# 2022.net
KiCad netlist of a schematic drawn in EAGLE
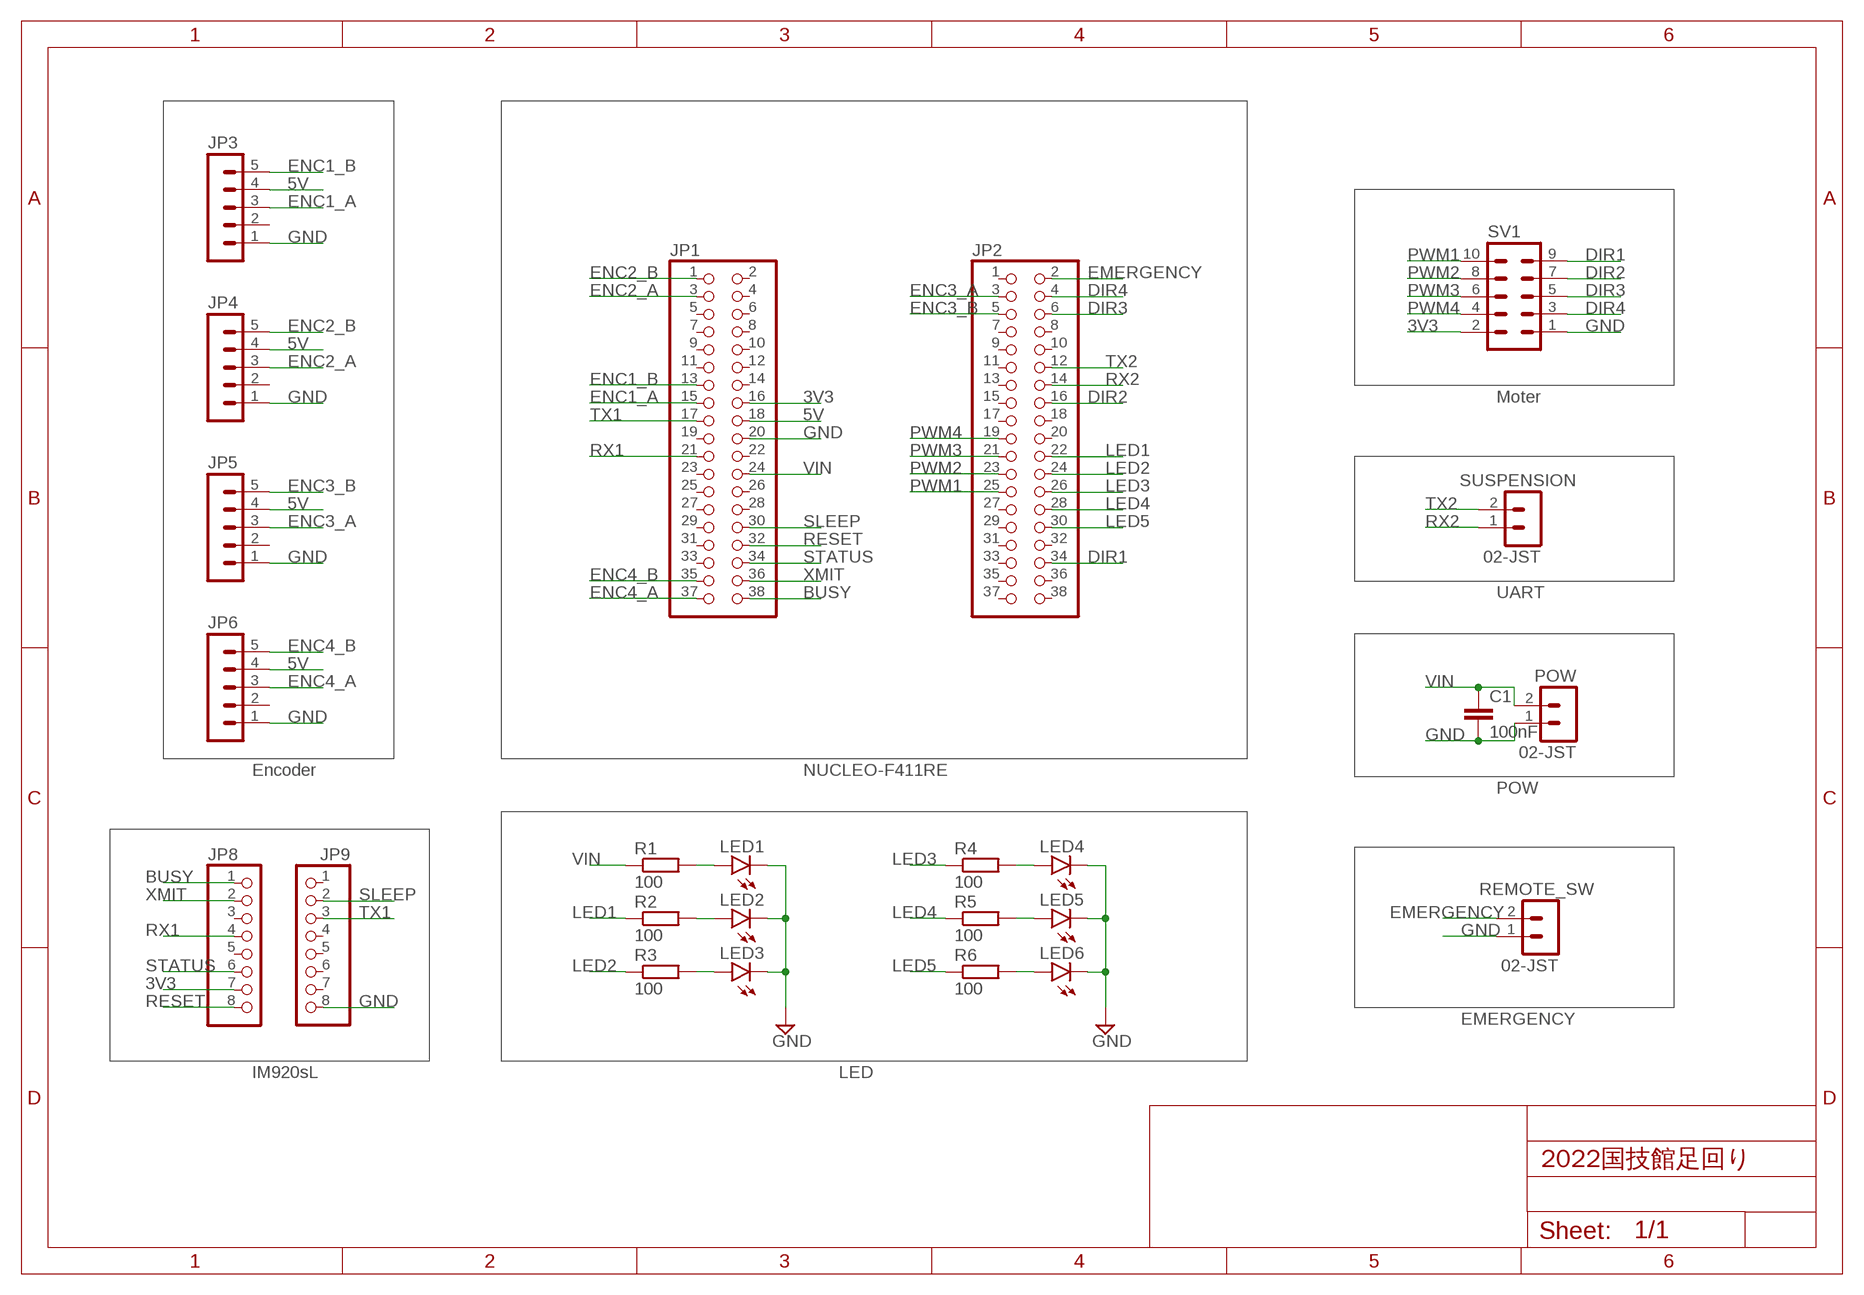
[diagram p0: schematic, sheet 1]

(export (version "E")
  (design (tool "Eeschema 10.0.6"))
  (components
    (comp (ref "C1")
      (value "100nF")
      (footprint "eagle-import:C025-024X044")
      (libsource (lib "eagle-import") (part "C-EU025-024X044"))
    )
    (comp (ref "JP1")
      (value "PINHD-2X19")
      (footprint "eagle-import:2X19")
      (libsource (lib "eagle-import") (part "PINHD-2X19"))
    )
    (comp (ref "JP2")
      (value "PINHD-2X19")
      (footprint "eagle-import:2X19")
      (libsource (lib "eagle-import") (part "PINHD-2X19"))
    )
    (comp (ref "JP3")
      (value "05-JST")
      (footprint "eagle-import:B5B-XH")
      (libsource (lib "eagle-import") (part "05-JST"))
    )
    (comp (ref "JP4")
      (value "05-JST")
      (footprint "eagle-import:B5B-XH")
      (libsource (lib "eagle-import") (part "05-JST"))
    )
    (comp (ref "JP5")
      (value "05-JST")
      (footprint "eagle-import:B5B-XH")
      (libsource (lib "eagle-import") (part "05-JST"))
    )
    (comp (ref "JP6")
      (value "05-JST")
      (footprint "eagle-import:B5B-XH")
      (libsource (lib "eagle-import") (part "05-JST"))
    )
    (comp (ref "JP8")
      (value "PINHD-1X8")
      (footprint "eagle-import:1X08")
      (libsource (lib "eagle-import") (part "PINHD-1X8"))
    )
    (comp (ref "JP9")
      (value "PINHD-1X8")
      (footprint "eagle-import:1X08")
      (libsource (lib "eagle-import") (part "PINHD-1X8"))
    )
    (comp (ref "LED1")
      (value "LED5MM")
      (footprint "eagle-import:LED5MM")
      (libsource (lib "eagle-import") (part "LED5MM"))
    )
    (comp (ref "LED2")
      (value "LED5MM")
      (footprint "eagle-import:LED5MM")
      (libsource (lib "eagle-import") (part "LED5MM"))
    )
    (comp (ref "LED3")
      (value "LED5MM")
      (footprint "eagle-import:LED5MM")
      (libsource (lib "eagle-import") (part "LED5MM"))
    )
    (comp (ref "LED4")
      (value "LED5MM")
      (footprint "eagle-import:LED5MM")
      (libsource (lib "eagle-import") (part "LED5MM"))
    )
    (comp (ref "LED5")
      (value "LED5MM")
      (footprint "eagle-import:LED5MM")
      (libsource (lib "eagle-import") (part "LED5MM"))
    )
    (comp (ref "LED6")
      (value "LED5MM")
      (footprint "eagle-import:LED5MM")
      (libsource (lib "eagle-import") (part "LED5MM"))
    )
    (comp (ref "POW")
      (value "02-JST")
      (footprint "eagle-import:B2B-XH")
      (libsource (lib "eagle-import") (part "02-JST"))
    )
    (comp (ref "R1")
      (value "100")
      (footprint "eagle-import:0204_7")
      (libsource (lib "eagle-import") (part "R-EU_0204/7"))
    )
    (comp (ref "R2")
      (value "100")
      (footprint "eagle-import:0207_2V")
      (libsource (lib "eagle-import") (part "R-EU_0207/2V"))
    )
    (comp (ref "R3")
      (value "100")
      (footprint "eagle-import:0207_2V")
      (libsource (lib "eagle-import") (part "R-EU_0207/2V"))
    )
    (comp (ref "R4")
      (value "100")
      (footprint "eagle-import:0207_2V")
      (libsource (lib "eagle-import") (part "R-EU_0207/2V"))
    )
    (comp (ref "R5")
      (value "100")
      (footprint "eagle-import:0207_2V")
      (libsource (lib "eagle-import") (part "R-EU_0207/2V"))
    )
    (comp (ref "R6")
      (value "100")
      (footprint "eagle-import:0207_2V")
      (libsource (lib "eagle-import") (part "R-EU_0207/2V"))
    )
    (comp (ref "REMOTE_SW")
      (value "02-JST")
      (footprint "eagle-import:B2B-XH")
      (libsource (lib "eagle-import") (part "02-JST"))
    )
    (comp (ref "SUSPENSION")
      (value "02-JST")
      (footprint "eagle-import:B2B-XH")
      (libsource (lib "eagle-import") (part "02-JST"))
    )
    (comp (ref "SV1")
      (value "ML10")
      (footprint "eagle-import:ML10")
      (libsource (lib "eagle-import") (part "ML10"))
    )
  )
  (nets
    (net (code "1") (name "/3V3") (class "Default")
      (node (ref "JP1") (pin "16") (pinfunction "16_16") (pintype "passive"))
      (node (ref "JP8") (pin "7") (pinfunction "7_7") (pintype "passive"))
      (node (ref "SV1") (pin "2") (pinfunction "2_2") (pintype "passive"))
    )
    (net (code "2") (name "/5V") (class "Default")
      (node (ref "JP1") (pin "18") (pinfunction "18_18") (pintype "passive"))
      (node (ref "JP3") (pin "4") (pinfunction "4_4") (pintype "passive"))
      (node (ref "JP4") (pin "4") (pinfunction "4_4") (pintype "passive"))
      (node (ref "JP5") (pin "4") (pinfunction "4_4") (pintype "passive"))
      (node (ref "JP6") (pin "4") (pinfunction "4_4") (pintype "passive"))
    )
    (net (code "3") (name "/BUSY") (class "Default")
      (node (ref "JP1") (pin "38") (pinfunction "38_38") (pintype "passive"))
      (node (ref "JP8") (pin "1") (pinfunction "1_1") (pintype "passive"))
    )
    (net (code "4") (name "/DIR1") (class "Default")
      (node (ref "JP2") (pin "34") (pinfunction "34_34") (pintype "passive"))
      (node (ref "SV1") (pin "9") (pinfunction "9_9") (pintype "passive"))
    )
    (net (code "5") (name "/DIR2") (class "Default")
      (node (ref "JP2") (pin "16") (pinfunction "16_16") (pintype "passive"))
      (node (ref "SV1") (pin "7") (pinfunction "7_7") (pintype "passive"))
    )
    (net (code "6") (name "/DIR3") (class "Default")
      (node (ref "JP2") (pin "6") (pinfunction "6_6") (pintype "passive"))
      (node (ref "SV1") (pin "5") (pinfunction "5_5") (pintype "passive"))
    )
    (net (code "7") (name "/DIR4") (class "Default")
      (node (ref "JP2") (pin "4") (pinfunction "4_4") (pintype "passive"))
      (node (ref "SV1") (pin "3") (pinfunction "3_3") (pintype "passive"))
    )
    (net (code "8") (name "/EMERGENCY") (class "Default")
      (node (ref "JP2") (pin "2") (pinfunction "2_2") (pintype "passive"))
      (node (ref "REMOTE_SW") (pin "2") (pinfunction "2_2") (pintype "passive"))
    )
    (net (code "9") (name "/ENC1_A") (class "Default")
      (node (ref "JP1") (pin "15") (pinfunction "15_15") (pintype "passive"))
      (node (ref "JP3") (pin "3") (pinfunction "3_3") (pintype "passive"))
    )
    (net (code "10") (name "/ENC1_B") (class "Default")
      (node (ref "JP1") (pin "13") (pinfunction "13_13") (pintype "passive"))
      (node (ref "JP3") (pin "5") (pinfunction "5_5") (pintype "passive"))
    )
    (net (code "11") (name "/ENC2_A") (class "Default")
      (node (ref "JP1") (pin "3") (pinfunction "3_3") (pintype "passive"))
      (node (ref "JP4") (pin "3") (pinfunction "3_3") (pintype "passive"))
    )
    (net (code "12") (name "/ENC2_B") (class "Default")
      (node (ref "JP1") (pin "1") (pinfunction "1_1") (pintype "passive"))
      (node (ref "JP4") (pin "5") (pinfunction "5_5") (pintype "passive"))
    )
    (net (code "13") (name "/ENC3_A") (class "Default")
      (node (ref "JP2") (pin "3") (pinfunction "3_3") (pintype "passive"))
      (node (ref "JP5") (pin "3") (pinfunction "3_3") (pintype "passive"))
    )
    (net (code "14") (name "/ENC3_B") (class "Default")
      (node (ref "JP2") (pin "5") (pinfunction "5_5") (pintype "passive"))
      (node (ref "JP5") (pin "5") (pinfunction "5_5") (pintype "passive"))
    )
    (net (code "15") (name "/ENC4_A") (class "Default")
      (node (ref "JP1") (pin "37") (pinfunction "37_37") (pintype "passive"))
      (node (ref "JP6") (pin "3") (pinfunction "3_3") (pintype "passive"))
    )
    (net (code "16") (name "/ENC4_B") (class "Default")
      (node (ref "JP1") (pin "35") (pinfunction "35_35") (pintype "passive"))
      (node (ref "JP6") (pin "5") (pinfunction "5_5") (pintype "passive"))
    )
    (net (code "17") (name "/LED1") (class "Default")
      (node (ref "JP2") (pin "22") (pinfunction "22_22") (pintype "passive"))
      (node (ref "R2") (pin "1") (pinfunction "1_1") (pintype "passive"))
    )
    (net (code "18") (name "/LED2") (class "Default")
      (node (ref "JP2") (pin "24") (pinfunction "24_24") (pintype "passive"))
      (node (ref "R3") (pin "1") (pinfunction "1_1") (pintype "passive"))
    )
    (net (code "19") (name "/LED3") (class "Default")
      (node (ref "JP2") (pin "26") (pinfunction "26_26") (pintype "passive"))
      (node (ref "R4") (pin "1") (pinfunction "1_1") (pintype "passive"))
    )
    (net (code "20") (name "/LED4") (class "Default")
      (node (ref "JP2") (pin "28") (pinfunction "28_28") (pintype "passive"))
      (node (ref "R5") (pin "1") (pinfunction "1_1") (pintype "passive"))
    )
    (net (code "21") (name "/LED5") (class "Default")
      (node (ref "JP2") (pin "30") (pinfunction "30_30") (pintype "passive"))
      (node (ref "R6") (pin "1") (pinfunction "1_1") (pintype "passive"))
    )
    (net (code "22") (name "/PWM1") (class "Default")
      (node (ref "JP2") (pin "25") (pinfunction "25_25") (pintype "passive"))
      (node (ref "SV1") (pin "10") (pinfunction "10_10") (pintype "passive"))
    )
    (net (code "23") (name "/PWM2") (class "Default")
      (node (ref "JP2") (pin "23") (pinfunction "23_23") (pintype "passive"))
      (node (ref "SV1") (pin "8") (pinfunction "8_8") (pintype "passive"))
    )
    (net (code "24") (name "/PWM3") (class "Default")
      (node (ref "JP2") (pin "21") (pinfunction "21_21") (pintype "passive"))
      (node (ref "SV1") (pin "6") (pinfunction "6_6") (pintype "passive"))
    )
    (net (code "25") (name "/PWM4") (class "Default")
      (node (ref "JP2") (pin "19") (pinfunction "19_19") (pintype "passive"))
      (node (ref "SV1") (pin "4") (pinfunction "4_4") (pintype "passive"))
    )
    (net (code "26") (name "/RESET") (class "Default")
      (node (ref "JP1") (pin "32") (pinfunction "32_32") (pintype "passive"))
      (node (ref "JP8") (pin "8") (pinfunction "8_8") (pintype "passive"))
    )
    (net (code "27") (name "/RX1") (class "Default")
      (node (ref "JP1") (pin "21") (pinfunction "21_21") (pintype "passive"))
      (node (ref "JP8") (pin "4") (pinfunction "4_4") (pintype "passive"))
    )
    (net (code "28") (name "/RX2") (class "Default")
      (node (ref "JP2") (pin "14") (pinfunction "14_14") (pintype "passive"))
      (node (ref "SUSPENSION") (pin "1") (pinfunction "1_1") (pintype "passive"))
    )
    (net (code "29") (name "/SLEEP") (class "Default")
      (node (ref "JP1") (pin "30") (pinfunction "30_30") (pintype "passive"))
      (node (ref "JP9") (pin "2") (pinfunction "2_2") (pintype "passive"))
    )
    (net (code "30") (name "/STATUS") (class "Default")
      (node (ref "JP1") (pin "34") (pinfunction "34_34") (pintype "passive"))
      (node (ref "JP8") (pin "6") (pinfunction "6_6") (pintype "passive"))
    )
    (net (code "31") (name "/TX1") (class "Default")
      (node (ref "JP1") (pin "17") (pinfunction "17_17") (pintype "passive"))
      (node (ref "JP9") (pin "3") (pinfunction "3_3") (pintype "passive"))
    )
    (net (code "32") (name "/TX2") (class "Default")
      (node (ref "JP2") (pin "12") (pinfunction "12_12") (pintype "passive"))
      (node (ref "SUSPENSION") (pin "2") (pinfunction "2_2") (pintype "passive"))
    )
    (net (code "33") (name "/VIN") (class "Default")
      (node (ref "C1") (pin "1") (pinfunction "1_1") (pintype "passive"))
      (node (ref "JP1") (pin "24") (pinfunction "24_24") (pintype "passive"))
      (node (ref "POW") (pin "2") (pinfunction "2_2") (pintype "passive"))
      (node (ref "R1") (pin "1") (pinfunction "1_1") (pintype "passive"))
    )
    (net (code "34") (name "/XMIT") (class "Default")
      (node (ref "JP1") (pin "36") (pinfunction "36_36") (pintype "passive"))
      (node (ref "JP8") (pin "2") (pinfunction "2_2") (pintype "passive"))
    )
    (net (code "35") (name "GND") (class "Default")
      (node (ref "C1") (pin "2") (pinfunction "2_2") (pintype "passive"))
      (node (ref "JP1") (pin "20") (pinfunction "20_20") (pintype "passive"))
      (node (ref "JP3") (pin "1") (pinfunction "1_1") (pintype "passive"))
      (node (ref "JP4") (pin "1") (pinfunction "1_1") (pintype "passive"))
      (node (ref "JP5") (pin "1") (pinfunction "1_1") (pintype "passive"))
      (node (ref "JP6") (pin "1") (pinfunction "1_1") (pintype "passive"))
      (node (ref "JP9") (pin "8") (pinfunction "8_8") (pintype "passive"))
      (node (ref "LED1") (pin "K") (pinfunction "C_K") (pintype "passive"))
      (node (ref "LED2") (pin "K") (pinfunction "C_K") (pintype "passive"))
      (node (ref "LED3") (pin "K") (pinfunction "C_K") (pintype "passive"))
      (node (ref "LED4") (pin "K") (pinfunction "C_K") (pintype "passive"))
      (node (ref "LED5") (pin "K") (pinfunction "C_K") (pintype "passive"))
      (node (ref "LED6") (pin "K") (pinfunction "C_K") (pintype "passive"))
      (node (ref "POW") (pin "1") (pinfunction "1_1") (pintype "passive"))
      (node (ref "REMOTE_SW") (pin "1") (pinfunction "1_1") (pintype "passive"))
      (node (ref "SV1") (pin "1") (pinfunction "1_1") (pintype "passive"))
    )
    (net (code "36") (name "Net-(LED1-PadA)") (class "Default")
      (node (ref "LED1") (pin "A") (pinfunction "A_A") (pintype "passive"))
      (node (ref "R1") (pin "2") (pinfunction "2_2") (pintype "passive"))
    )
    (net (code "37") (name "Net-(LED2-PadA)") (class "Default")
      (node (ref "LED2") (pin "A") (pinfunction "A_A") (pintype "passive"))
      (node (ref "R2") (pin "2") (pinfunction "2_2") (pintype "passive"))
    )
    (net (code "38") (name "Net-(LED3-PadA)") (class "Default")
      (node (ref "LED3") (pin "A") (pinfunction "A_A") (pintype "passive"))
      (node (ref "R3") (pin "2") (pinfunction "2_2") (pintype "passive"))
    )
    (net (code "39") (name "Net-(LED4-PadA)") (class "Default")
      (node (ref "LED4") (pin "A") (pinfunction "A_A") (pintype "passive"))
      (node (ref "R4") (pin "2") (pinfunction "2_2") (pintype "passive"))
    )
    (net (code "40") (name "Net-(LED5-PadA)") (class "Default")
      (node (ref "LED5") (pin "A") (pinfunction "A_A") (pintype "passive"))
      (node (ref "R5") (pin "2") (pinfunction "2_2") (pintype "passive"))
    )
    (net (code "41") (name "Net-(LED6-PadA)") (class "Default")
      (node (ref "LED6") (pin "A") (pinfunction "A_A") (pintype "passive"))
      (node (ref "R6") (pin "2") (pinfunction "2_2") (pintype "passive"))
    )
    (net (code "42") (name "unconnected-(JP1-Pad2)") (class "Default")
      (node (ref "JP1") (pin "2") (pinfunction "2_2") (pintype "passive"))
    )
    (net (code "43") (name "unconnected-(JP1-Pad4)") (class "Default")
      (node (ref "JP1") (pin "4") (pinfunction "4_4") (pintype "passive"))
    )
    (net (code "44") (name "unconnected-(JP1-Pad5)") (class "Default")
      (node (ref "JP1") (pin "5") (pinfunction "5_5") (pintype "passive"))
    )
    (net (code "45") (name "unconnected-(JP1-Pad6)") (class "Default")
      (node (ref "JP1") (pin "6") (pinfunction "6_6") (pintype "passive"))
    )
    (net (code "46") (name "unconnected-(JP1-Pad7)") (class "Default")
      (node (ref "JP1") (pin "7") (pinfunction "7_7") (pintype "passive"))
    )
    (net (code "47") (name "unconnected-(JP1-Pad8)") (class "Default")
      (node (ref "JP1") (pin "8") (pinfunction "8_8") (pintype "passive"))
    )
    (net (code "48") (name "unconnected-(JP1-Pad9)") (class "Default")
      (node (ref "JP1") (pin "9") (pinfunction "9_9") (pintype "passive"))
    )
    (net (code "49") (name "unconnected-(JP1-Pad10)") (class "Default")
      (node (ref "JP1") (pin "10") (pinfunction "10_10") (pintype "passive"))
    )
    (net (code "50") (name "unconnected-(JP1-Pad11)") (class "Default")
      (node (ref "JP1") (pin "11") (pinfunction "11_11") (pintype "passive"))
    )
    (net (code "51") (name "unconnected-(JP1-Pad12)") (class "Default")
      (node (ref "JP1") (pin "12") (pinfunction "12_12") (pintype "passive"))
    )
    (net (code "52") (name "unconnected-(JP1-Pad14)") (class "Default")
      (node (ref "JP1") (pin "14") (pinfunction "14_14") (pintype "passive"))
    )
    (net (code "53") (name "unconnected-(JP1-Pad19)") (class "Default")
      (node (ref "JP1") (pin "19") (pinfunction "19_19") (pintype "passive"))
    )
    (net (code "54") (name "unconnected-(JP1-Pad22)") (class "Default")
      (node (ref "JP1") (pin "22") (pinfunction "22_22") (pintype "passive"))
    )
    (net (code "55") (name "unconnected-(JP1-Pad23)") (class "Default")
      (node (ref "JP1") (pin "23") (pinfunction "23_23") (pintype "passive"))
    )
    (net (code "56") (name "unconnected-(JP1-Pad25)") (class "Default")
      (node (ref "JP1") (pin "25") (pinfunction "25_25") (pintype "passive"))
    )
    (net (code "57") (name "unconnected-(JP1-Pad26)") (class "Default")
      (node (ref "JP1") (pin "26") (pinfunction "26_26") (pintype "passive"))
    )
    (net (code "58") (name "unconnected-(JP1-Pad27)") (class "Default")
      (node (ref "JP1") (pin "27") (pinfunction "27_27") (pintype "passive"))
    )
    (net (code "59") (name "unconnected-(JP1-Pad28)") (class "Default")
      (node (ref "JP1") (pin "28") (pinfunction "28_28") (pintype "passive"))
    )
    (net (code "60") (name "unconnected-(JP1-Pad29)") (class "Default")
      (node (ref "JP1") (pin "29") (pinfunction "29_29") (pintype "passive"))
    )
    (net (code "61") (name "unconnected-(JP1-Pad31)") (class "Default")
      (node (ref "JP1") (pin "31") (pinfunction "31_31") (pintype "passive"))
    )
    (net (code "62") (name "unconnected-(JP1-Pad33)") (class "Default")
      (node (ref "JP1") (pin "33") (pinfunction "33_33") (pintype "passive"))
    )
    (net (code "63") (name "unconnected-(JP2-Pad1)") (class "Default")
      (node (ref "JP2") (pin "1") (pinfunction "1_1") (pintype "passive"))
    )
    (net (code "64") (name "unconnected-(JP2-Pad7)") (class "Default")
      (node (ref "JP2") (pin "7") (pinfunction "7_7") (pintype "passive"))
    )
    (net (code "65") (name "unconnected-(JP2-Pad8)") (class "Default")
      (node (ref "JP2") (pin "8") (pinfunction "8_8") (pintype "passive"))
    )
    (net (code "66") (name "unconnected-(JP2-Pad9)") (class "Default")
      (node (ref "JP2") (pin "9") (pinfunction "9_9") (pintype "passive"))
    )
    (net (code "67") (name "unconnected-(JP2-Pad10)") (class "Default")
      (node (ref "JP2") (pin "10") (pinfunction "10_10") (pintype "passive"))
    )
    (net (code "68") (name "unconnected-(JP2-Pad11)") (class "Default")
      (node (ref "JP2") (pin "11") (pinfunction "11_11") (pintype "passive"))
    )
    (net (code "69") (name "unconnected-(JP2-Pad13)") (class "Default")
      (node (ref "JP2") (pin "13") (pinfunction "13_13") (pintype "passive"))
    )
    (net (code "70") (name "unconnected-(JP2-Pad15)") (class "Default")
      (node (ref "JP2") (pin "15") (pinfunction "15_15") (pintype "passive"))
    )
    (net (code "71") (name "unconnected-(JP2-Pad17)") (class "Default")
      (node (ref "JP2") (pin "17") (pinfunction "17_17") (pintype "passive"))
    )
    (net (code "72") (name "unconnected-(JP2-Pad18)") (class "Default")
      (node (ref "JP2") (pin "18") (pinfunction "18_18") (pintype "passive"))
    )
    (net (code "73") (name "unconnected-(JP2-Pad20)") (class "Default")
      (node (ref "JP2") (pin "20") (pinfunction "20_20") (pintype "passive"))
    )
    (net (code "74") (name "unconnected-(JP2-Pad27)") (class "Default")
      (node (ref "JP2") (pin "27") (pinfunction "27_27") (pintype "passive"))
    )
    (net (code "75") (name "unconnected-(JP2-Pad29)") (class "Default")
      (node (ref "JP2") (pin "29") (pinfunction "29_29") (pintype "passive"))
    )
    (net (code "76") (name "unconnected-(JP2-Pad31)") (class "Default")
      (node (ref "JP2") (pin "31") (pinfunction "31_31") (pintype "passive"))
    )
    (net (code "77") (name "unconnected-(JP2-Pad32)") (class "Default")
      (node (ref "JP2") (pin "32") (pinfunction "32_32") (pintype "passive"))
    )
    (net (code "78") (name "unconnected-(JP2-Pad33)") (class "Default")
      (node (ref "JP2") (pin "33") (pinfunction "33_33") (pintype "passive"))
    )
    (net (code "79") (name "unconnected-(JP2-Pad35)") (class "Default")
      (node (ref "JP2") (pin "35") (pinfunction "35_35") (pintype "passive"))
    )
    (net (code "80") (name "unconnected-(JP2-Pad36)") (class "Default")
      (node (ref "JP2") (pin "36") (pinfunction "36_36") (pintype "passive"))
    )
    (net (code "81") (name "unconnected-(JP2-Pad37)") (class "Default")
      (node (ref "JP2") (pin "37") (pinfunction "37_37") (pintype "passive"))
    )
    (net (code "82") (name "unconnected-(JP2-Pad38)") (class "Default")
      (node (ref "JP2") (pin "38") (pinfunction "38_38") (pintype "passive"))
    )
    (net (code "83") (name "unconnected-(JP3-Pad2)") (class "Default")
      (node (ref "JP3") (pin "2") (pinfunction "2_2") (pintype "passive"))
    )
    (net (code "84") (name "unconnected-(JP4-Pad2)") (class "Default")
      (node (ref "JP4") (pin "2") (pinfunction "2_2") (pintype "passive"))
    )
    (net (code "85") (name "unconnected-(JP5-Pad2)") (class "Default")
      (node (ref "JP5") (pin "2") (pinfunction "2_2") (pintype "passive"))
    )
    (net (code "86") (name "unconnected-(JP6-Pad2)") (class "Default")
      (node (ref "JP6") (pin "2") (pinfunction "2_2") (pintype "passive"))
    )
    (net (code "87") (name "unconnected-(JP8-Pad3)") (class "Default")
      (node (ref "JP8") (pin "3") (pinfunction "3_3") (pintype "passive"))
    )
    (net (code "88") (name "unconnected-(JP8-Pad5)") (class "Default")
      (node (ref "JP8") (pin "5") (pinfunction "5_5") (pintype "passive"))
    )
    (net (code "89") (name "unconnected-(JP9-Pad1)") (class "Default")
      (node (ref "JP9") (pin "1") (pinfunction "1_1") (pintype "passive"))
    )
    (net (code "90") (name "unconnected-(JP9-Pad4)") (class "Default")
      (node (ref "JP9") (pin "4") (pinfunction "4_4") (pintype "passive"))
    )
    (net (code "91") (name "unconnected-(JP9-Pad5)") (class "Default")
      (node (ref "JP9") (pin "5") (pinfunction "5_5") (pintype "passive"))
    )
    (net (code "92") (name "unconnected-(JP9-Pad6)") (class "Default")
      (node (ref "JP9") (pin "6") (pinfunction "6_6") (pintype "passive"))
    )
    (net (code "93") (name "unconnected-(JP9-Pad7)") (class "Default")
      (node (ref "JP9") (pin "7") (pinfunction "7_7") (pintype "passive"))
    )
  )
)
